# OldETHERNET.net
KiCad netlist of a schematic drawn in Altium Designer
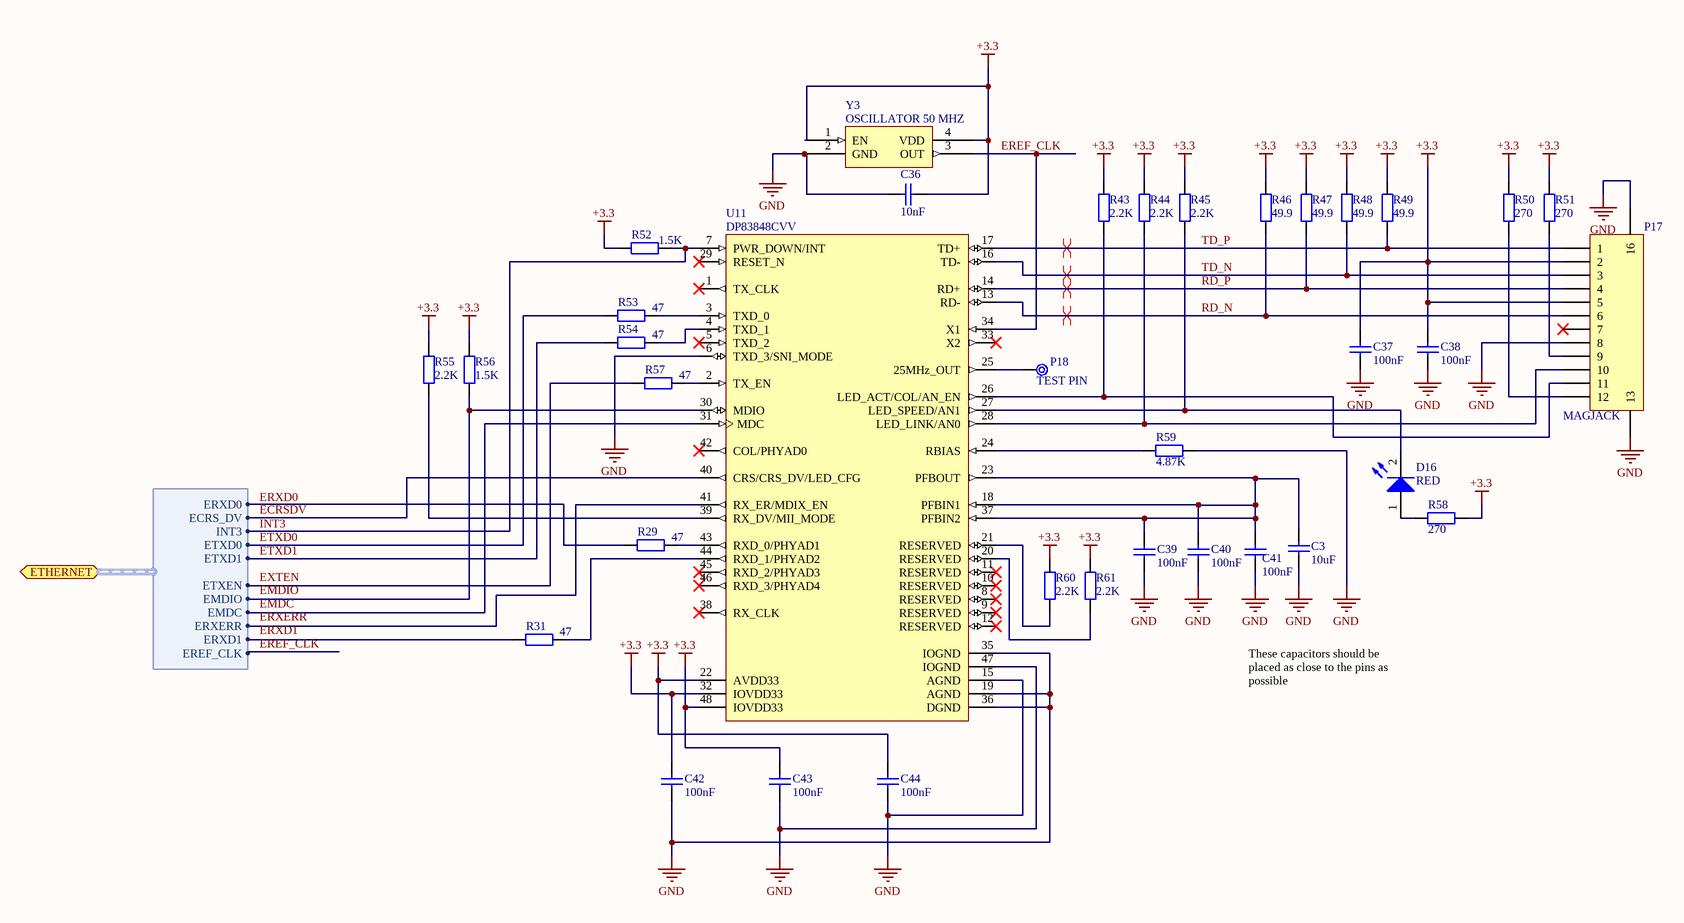
[diagram p0: OldETHERNET.SchDoc]

(export (version "E")
  (design (tool "Eeschema 10.0.6"))
  (components
    (comp (ref "C3")
      (value "10uF")
      (footprint "C0805")
      (description "Capacitor")
      (fields
        (field (name "MANUFACTURER") "YAGEO")
        (field (name "MANUFACTURER PART NUMBER") "CC0805KKX5R5BB106")
      )
      (libsource (lib "BRA") (part "Cap 0805 1uF"))
    )
    (comp (ref "C36")
      (value "10nF")
      (footprint "C0805")
      (description "Capacitor")
      (fields
        (field (name "MANUFACTURER") "MULTICOMP")
        (field (name "MANUFACTURER PART NUMBER") "MC0805B103M500CT")
      )
      (libsource (lib "BRA") (part "Cap 0805 10nF"))
    )
    (comp (ref "C37")
      (value "100nF")
      (footprint "C0805")
      (description "Capacitor")
      (fields
        (field (name "MANUFACTURER") "MULTICOMP")
        (field (name "MANUFACTURER PART NUMBER") "MCCA000296")
      )
      (libsource (lib "BRA") (part "Cap 0805 100nF"))
    )
    (comp (ref "C38")
      (value "100nF")
      (footprint "C0805")
      (description "Capacitor")
      (fields
        (field (name "MANUFACTURER") "MULTICOMP")
        (field (name "MANUFACTURER PART NUMBER") "MCCA000296")
      )
      (libsource (lib "BRA") (part "Cap 0805 100nF"))
    )
    (comp (ref "C39")
      (value "100nF")
      (footprint "C0805")
      (description "Capacitor")
      (fields
        (field (name "MANUFACTURER") "MULTICOMP")
        (field (name "MANUFACTURER PART NUMBER") "MCCA000296")
      )
      (libsource (lib "BRA") (part "Cap 0805 100nF"))
    )
    (comp (ref "C40")
      (value "100nF")
      (footprint "C0805")
      (description "Capacitor")
      (fields
        (field (name "MANUFACTURER") "MULTICOMP")
        (field (name "MANUFACTURER PART NUMBER") "MCCA000296")
      )
      (libsource (lib "BRA") (part "Cap 0805 100nF"))
    )
    (comp (ref "C41")
      (value "100nF")
      (footprint "C0805")
      (description "Capacitor")
      (fields
        (field (name "MANUFACTURER") "MULTICOMP")
        (field (name "MANUFACTURER PART NUMBER") "MCCA000296")
      )
      (libsource (lib "BRA") (part "Cap 0805 100nF"))
    )
    (comp (ref "C42")
      (value "100nF")
      (footprint "C0805")
      (description "Capacitor")
      (fields
        (field (name "MANUFACTURER") "MULTICOMP")
        (field (name "MANUFACTURER PART NUMBER") "MCCA000296")
      )
      (libsource (lib "BRA") (part "Cap 0805 100nF"))
    )
    (comp (ref "C43")
      (value "100nF")
      (footprint "C0805")
      (description "Capacitor")
      (fields
        (field (name "MANUFACTURER") "MULTICOMP")
        (field (name "MANUFACTURER PART NUMBER") "MCCA000296")
      )
      (libsource (lib "BRA") (part "Cap 0805 100nF"))
    )
    (comp (ref "C44")
      (value "100nF")
      (footprint "C0805")
      (description "Capacitor")
      (fields
        (field (name "MANUFACTURER") "MULTICOMP")
        (field (name "MANUFACTURER PART NUMBER") "MCCA000296")
      )
      (libsource (lib "BRA") (part "Cap 0805 100nF"))
    )
    (comp (ref "D16")
      (value "HSMH-C190")
      (footprint "SYLANN:0603-LEDR")
      (description "Surface Mount Chip LED, Red")
      (fields
        (field (name "MANUFACTURER") "AVAGO TECHNOLOGIES")
        (field (name "MANUFACTURER PART NUMBER") "HSMH-C190.")
        (field (name "COULEUR") "RED")
        (field (name "LONGUEUR/HAUTEUR") "1.6")
      )
      (libsource (lib "Avago Optoelectronic LED") (part "HSMH-C190"))
    )
    (comp (ref "P17")
      (value "MAGJACK")
      (footprint "RJ45_8+LED")
      (description "Header, 12-Pin")
      (fields
        (field (name "MANUFACTURER") "STEWART CONNECTOR")
        (field (name "MANUFACTURER PART NUMBER") "SI-60062-F")
        (field (name "PUBLISHER") "Altium Limited")
      )
      (libsource (lib "MAIN BOARD CERES") (part "Header 12"))
    )
    (comp (ref "P18") (value "TEST PIN") (footprint "TP") (libsource (lib "UTIL_Library") (part "TEST PIN")))
    (comp (ref "R29")
      (value "47")
      (footprint "R0805")
      (description "Resistor")
      (fields
        (field (name "MANUFACTURER") "MULTICOMP")
        (field (name "MANUFACTURER PART NUMBER") "MC0063W0603147R")
      )
      (libsource (lib "BRA") (part "Resistor 0805 47"))
    )
    (comp (ref "R31")
      (value "47")
      (footprint "R0805")
      (description "Resistor")
      (fields
        (field (name "MANUFACTURER") "MULTICOMP")
        (field (name "MANUFACTURER PART NUMBER") "MC0063W0603147R")
      )
      (libsource (lib "BRA") (part "Resistor 0805 47"))
    )
    (comp (ref "R43")
      (value "2.2K")
      (footprint "R0805")
      (description "Resistor")
      (fields
        (field (name "MANUFACTURER") "MULTICOMP")
        (field (name "MANUFACTURER PART NUMBER") "MC01W080512K2")
      )
      (libsource (lib "BRA") (part "Resistor 0805 2.2K"))
    )
    (comp (ref "R44")
      (value "2.2K")
      (footprint "R0805")
      (description "Resistor")
      (fields
        (field (name "MANUFACTURER") "MULTICOMP")
        (field (name "MANUFACTURER PART NUMBER") "MC01W080512K2")
      )
      (libsource (lib "BRA") (part "Resistor 0805 2.2K"))
    )
    (comp (ref "R45")
      (value "2.2K")
      (footprint "R0805")
      (description "Resistor")
      (fields
        (field (name "MANUFACTURER") "MULTICOMP")
        (field (name "MANUFACTURER PART NUMBER") "MC01W080512K2")
      )
      (libsource (lib "BRA") (part "Resistor 0805 2.2K"))
    )
    (comp (ref "R46")
      (value "49.9")
      (footprint "R0805")
      (description "Resistor")
      (fields
        (field (name "MANUFACTURER") "MULTICOMP")
        (field (name "MANUFACTURER PART NUMBER") "MC01W0805149R9")
      )
      (libsource (lib "BRA") (part "Resistor 0805 49.9"))
    )
    (comp (ref "R47")
      (value "49.9")
      (footprint "R0805")
      (description "Resistor")
      (fields
        (field (name "MANUFACTURER") "MULTICOMP")
        (field (name "MANUFACTURER PART NUMBER") "MC01W0805149R9")
      )
      (libsource (lib "BRA") (part "Resistor 0805 49.9"))
    )
    (comp (ref "R48")
      (value "49.9")
      (footprint "R0805")
      (description "Resistor")
      (fields
        (field (name "MANUFACTURER") "MULTICOMP")
        (field (name "MANUFACTURER PART NUMBER") "MC01W0805149R9")
      )
      (libsource (lib "BRA") (part "Resistor 0805 49.9"))
    )
    (comp (ref "R49")
      (value "49.9")
      (footprint "R0805")
      (description "Resistor")
      (fields
        (field (name "MANUFACTURER") "MULTICOMP")
        (field (name "MANUFACTURER PART NUMBER") "MC01W0805149R9")
      )
      (libsource (lib "BRA") (part "Resistor 0805 49.9"))
    )
    (comp (ref "R50")
      (value "270")
      (footprint "R0805")
      (description "Resistor")
      (fields
        (field (name "MANUFACTURER") "MULTICOMP")
        (field (name "MANUFACTURER PART NUMBER") "MC01W08051270R")
      )
      (libsource (lib "BRA") (part "Resistor 0805 270"))
    )
    (comp (ref "R51")
      (value "270")
      (footprint "R0805")
      (description "Resistor")
      (fields
        (field (name "MANUFACTURER") "MULTICOMP")
        (field (name "MANUFACTURER PART NUMBER") "MC01W08051270R")
      )
      (libsource (lib "BRA") (part "Resistor 0805 270"))
    )
    (comp (ref "R52")
      (value "1.5K")
      (footprint "R0805")
      (description "Resistor")
      (fields
        (field (name "MANUFACTURER") "MULTICOMP")
        (field (name "MANUFACTURER PART NUMBER") "MC00625W040211K5")
      )
      (libsource (lib "BRA") (part "Resistor 0805 1.5K"))
    )
    (comp (ref "R53")
      (value "47")
      (footprint "R0805")
      (description "Resistor")
      (fields
        (field (name "MANUFACTURER") "MULTICOMP")
        (field (name "MANUFACTURER PART NUMBER") "MC0063W0603147R")
      )
      (libsource (lib "BRA") (part "Resistor 0805 47"))
    )
    (comp (ref "R54")
      (value "47")
      (footprint "R0805")
      (description "Resistor")
      (fields
        (field (name "MANUFACTURER") "MULTICOMP")
        (field (name "MANUFACTURER PART NUMBER") "MC0063W0603147R")
      )
      (libsource (lib "BRA") (part "Resistor 0805 47"))
    )
    (comp (ref "R55")
      (value "2.2K")
      (footprint "R0805")
      (description "Resistor")
      (fields
        (field (name "MANUFACTURER") "MULTICOMP")
        (field (name "MANUFACTURER PART NUMBER") "MC01W080512K2")
      )
      (libsource (lib "BRA") (part "Resistor 0805 2.2K"))
    )
    (comp (ref "R56")
      (value "1.5K")
      (footprint "R0805")
      (description "Resistor")
      (fields
        (field (name "MANUFACTURER") "MULTICOMP")
        (field (name "MANUFACTURER PART NUMBER") "MC00625W040211K5")
      )
      (libsource (lib "") (part "Resistor 0805 1.5K_1"))
    )
    (comp (ref "R57")
      (value "47")
      (footprint "R0805")
      (description "Resistor")
      (fields
        (field (name "MANUFACTURER") "MULTICOMP")
        (field (name "MANUFACTURER PART NUMBER") "MC0063W0603147R")
      )
      (libsource (lib "BRA") (part "Resistor 0805 47"))
    )
    (comp (ref "R58")
      (value "270")
      (footprint "R0805")
      (description "Resistor")
      (fields
        (field (name "MANUFACTURER") "MULTICOMP")
        (field (name "MANUFACTURER PART NUMBER") "MC01W08051270R")
      )
      (libsource (lib "BRA") (part "Resistor 0805 1K"))
    )
    (comp (ref "R59")
      (value "4.87K")
      (footprint "R0805")
      (description "Resistor")
      (fields
        (field (name "MANUFACTURER") "MULTICOMP")
        (field (name "MANUFACTURER PART NUMBER") "MC01W080514K87")
      )
      (libsource (lib "BRA") (part "Resistor 0805"))
    )
    (comp (ref "R60")
      (value "2.2K")
      (footprint "R0805")
      (description "Resistor")
      (fields
        (field (name "MANUFACTURER") "MULTICOMP")
        (field (name "MANUFACTURER PART NUMBER") "MC01W080512K2")
      )
      (libsource (lib "BRA") (part "Resistor 0805 2.2K"))
    )
    (comp (ref "R61")
      (value "2.2K")
      (footprint "R0805")
      (description "Resistor")
      (fields
        (field (name "MANUFACTURER") "MULTICOMP")
        (field (name "MANUFACTURER PART NUMBER") "MC01W080512K2")
      )
      (libsource (lib "BRA") (part "Resistor 0805 2.2K"))
    )
    (comp (ref "U11")
      (value "DP83848CVV")
      (footprint "LLP40P600X600X80_HS-41N")
      (fields
        (field (name "MANUFACTURER") "TEXAS INSTRUMENTS")
        (field (name "MANUFACTURER PART NUMBER") "DP83848MSQ/NOPB")
      )
      (libsource (lib "NSC Interface") (part "DP83848CVV"))
    )
    (comp (ref "Y3")
      (value "OSCILLATOR 50 MHZ")
      (footprint "X3225")
      (description "50 MHZ 3.3Vdc CMOS SMD CRYSTAL CLOCK OSCILLATOR")
      (fields
        (field (name "MANUFACTURER") "ABRACON")
        (field (name "MANUFACTURER PART NUMBER") "ASE-50.000MHZ-LR-T")
      )
      (libsource (lib "BRA") (part "OSCILLLATOR"))
    )
  )
  (nets
    (net (code "2") (name "+3.3") (class "Default")
      (node (ref "C36") (pin "1") (pinfunction "1_1") (pintype "passive"))
      (node (ref "C37") (pin "1") (pinfunction "1_1") (pintype "passive"))
      (node (ref "C38") (pin "1") (pinfunction "1_1") (pintype "passive"))
      (node (ref "C42") (pin "1") (pinfunction "1_1") (pintype "passive"))
      (node (ref "C43") (pin "1") (pinfunction "1_1") (pintype "passive"))
      (node (ref "C44") (pin "1") (pinfunction "1_1") (pintype "passive"))
      (node (ref "P17") (pin "2") (pinfunction "2_2") (pintype "passive"))
      (node (ref "P17") (pin "5") (pinfunction "5_5") (pintype "passive"))
      (node (ref "R43") (pin "2") (pinfunction "2_2") (pintype "passive"))
      (node (ref "R44") (pin "2") (pinfunction "2_2") (pintype "passive"))
      (node (ref "R45") (pin "2") (pinfunction "2_2") (pintype "passive"))
      (node (ref "R46") (pin "2") (pinfunction "2_2") (pintype "passive"))
      (node (ref "R47") (pin "2") (pinfunction "2_2") (pintype "passive"))
      (node (ref "R48") (pin "2") (pinfunction "2_2") (pintype "passive"))
      (node (ref "R49") (pin "2") (pinfunction "2_2") (pintype "passive"))
      (node (ref "R50") (pin "2") (pinfunction "2_2") (pintype "passive"))
      (node (ref "R51") (pin "2") (pinfunction "2_2") (pintype "passive"))
      (node (ref "R52") (pin "2") (pinfunction "2_2") (pintype "passive"))
      (node (ref "R55") (pin "2") (pinfunction "2_2") (pintype "passive"))
      (node (ref "R56") (pin "2") (pinfunction "2_2") (pintype "passive"))
      (node (ref "R58") (pin "1") (pinfunction "1_1") (pintype "passive"))
      (node (ref "R60") (pin "2") (pinfunction "2_2") (pintype "passive"))
      (node (ref "R61") (pin "2") (pinfunction "2_2") (pintype "passive"))
      (node (ref "U11") (pin "22") (pinfunction "AVDD33_22") (pintype "power_in"))
      (node (ref "U11") (pin "32") (pinfunction "IOVDD33_32") (pintype "power_in"))
      (node (ref "U11") (pin "48") (pinfunction "IOVDD33_48") (pintype "power_in"))
      (node (ref "Y3") (pin "1") (pinfunction "EN_1") (pintype "input"))
      (node (ref "Y3") (pin "4") (pinfunction "VDD_4") (pintype "power_in"))
    )
    (net (code "3") (name "/ECRSDV") (class "Default")
      (node (ref "U11") (pin "40") (pinfunction "CRS/CRS_DV/LED_CFG_40") (pintype "output"))
    )
    (net (code "6") (name "/EREF_CLK") (class "Default")
      (node (ref "U11") (pin "34") (pinfunction "X1_34") (pintype "input"))
      (node (ref "Y3") (pin "3") (pinfunction "OUT_3") (pintype "output"))
    )
    (net (code "12") (name "/ETXEN") (class "Default")
      (node (ref "R57") (pin "2") (pinfunction "2_2") (pintype "passive"))
    )
    (net (code "15") (name "/RD_N") (class "Default")
      (node (ref "P17") (pin "6") (pinfunction "6_6") (pintype "passive"))
      (node (ref "R46") (pin "1") (pinfunction "1_1") (pintype "passive"))
      (node (ref "U11") (pin "13") (pinfunction "RD-_13") (pintype "bidirectional"))
    )
    (net (code "16") (name "/RD_P") (class "Default")
      (node (ref "P17") (pin "4") (pinfunction "4_4") (pintype "passive"))
      (node (ref "R47") (pin "1") (pinfunction "1_1") (pintype "passive"))
      (node (ref "U11") (pin "14") (pinfunction "RD+_14") (pintype "bidirectional"))
    )
    (net (code "17") (name "/TD_N") (class "Default")
      (node (ref "P17") (pin "3") (pinfunction "3_3") (pintype "passive"))
      (node (ref "R48") (pin "1") (pinfunction "1_1") (pintype "passive"))
      (node (ref "U11") (pin "16") (pinfunction "TD-_16") (pintype "bidirectional"))
    )
    (net (code "18") (name "/TD_P") (class "Default")
      (node (ref "P17") (pin "1") (pinfunction "1_1") (pintype "passive"))
      (node (ref "R49") (pin "1") (pinfunction "1_1") (pintype "passive"))
      (node (ref "U11") (pin "17") (pinfunction "TD+_17") (pintype "bidirectional"))
    )
    (net (code "20") (name "GND") (class "Default")
      (node (ref "C3") (pin "2") (pinfunction "2_2") (pintype "passive"))
      (node (ref "C36") (pin "2") (pinfunction "2_2") (pintype "passive"))
      (node (ref "C37") (pin "2") (pinfunction "2_2") (pintype "passive"))
      (node (ref "C38") (pin "2") (pinfunction "2_2") (pintype "passive"))
      (node (ref "C39") (pin "2") (pinfunction "2_2") (pintype "passive"))
      (node (ref "C40") (pin "2") (pinfunction "2_2") (pintype "passive"))
      (node (ref "C41") (pin "2") (pinfunction "2_2") (pintype "passive"))
      (node (ref "C42") (pin "2") (pinfunction "2_2") (pintype "passive"))
      (node (ref "C43") (pin "2") (pinfunction "2_2") (pintype "passive"))
      (node (ref "C44") (pin "2") (pinfunction "2_2") (pintype "passive"))
      (node (ref "P17") (pin "13") (pinfunction "13_13") (pintype "passive"))
      (node (ref "P17") (pin "16") (pinfunction "16_16") (pintype "passive"))
      (node (ref "P17") (pin "8") (pinfunction "8_8") (pintype "passive"))
      (node (ref "R59") (pin "1") (pinfunction "1_1") (pintype "passive"))
      (node (ref "U11") (pin "15") (pinfunction "AGND_15") (pintype "power_in"))
      (node (ref "U11") (pin "19") (pinfunction "AGND_19") (pintype "power_in"))
      (node (ref "U11") (pin "35") (pinfunction "IOGND_35") (pintype "power_in"))
      (node (ref "U11") (pin "36") (pinfunction "DGND_36") (pintype "power_in"))
      (node (ref "U11") (pin "47") (pinfunction "IOGND_47") (pintype "power_in"))
      (node (ref "U11") (pin "6") (pinfunction "TXD_3/SNI_MODE_6") (pintype "bidirectional"))
      (node (ref "Y3") (pin "2") (pinfunction "GND_2") (pintype "power_in"))
    )
    (net (code "21") (name "Net-(D16-A)") (class "Default")
      (node (ref "D16") (pin "1") (pinfunction "A_1") (pintype "passive"))
      (node (ref "R58") (pin "2") (pinfunction "2_2") (pintype "passive"))
    )
    (net (code "22") (name "Net-(D16-K)") (class "Default")
      (node (ref "D16") (pin "2") (pinfunction "K_2") (pintype "passive"))
      (node (ref "R45") (pin "1") (pinfunction "1_1") (pintype "passive"))
      (node (ref "U11") (pin "27") (pinfunction "LED_SPEED/AN1_27") (pintype "output"))
    )
    (net (code "23") (name "Net-(P17-Pad9)") (class "Default")
      (node (ref "P17") (pin "9") (pinfunction "9_9") (pintype "passive"))
      (node (ref "R51") (pin "1") (pinfunction "1_1") (pintype "passive"))
    )
    (net (code "24") (name "Net-(P17-Pad12)") (class "Default")
      (node (ref "P17") (pin "12") (pinfunction "12_12") (pintype "passive"))
      (node (ref "R50") (pin "1") (pinfunction "1_1") (pintype "passive"))
    )
    (net (code "25") (name "Net-(R60-Pad1)") (class "Default")
      (node (ref "R60") (pin "1") (pinfunction "1_1") (pintype "passive"))
      (node (ref "U11") (pin "21") (pinfunction "RESERVED_21") (pintype "bidirectional"))
    )
    (net (code "26") (name "Net-(R61-Pad1)") (class "Default")
      (node (ref "R61") (pin "1") (pinfunction "1_1") (pintype "passive"))
      (node (ref "U11") (pin "20") (pinfunction "RESERVED_20") (pintype "bidirectional"))
    )
    (net (code "27") (name "Net-(U11-25MHz_OUT)") (class "Default")
      (node (ref "P18") (pin "1") (pinfunction "1_1") (pintype "passive"))
      (node (ref "U11") (pin "25") (pinfunction "25MHz_OUT_25") (pintype "output"))
    )
    (net (code "28") (name "Net-(U11-LED_ACT{slash}COL{slash}AN_EN)") (class "Default")
      (node (ref "P17") (pin "11") (pinfunction "11_11") (pintype "passive"))
      (node (ref "R43") (pin "1") (pinfunction "1_1") (pintype "passive"))
      (node (ref "U11") (pin "26") (pinfunction "LED_ACT/COL/AN_EN_26") (pintype "output"))
    )
    (net (code "29") (name "Net-(U11-LED_LINK{slash}AN0)") (class "Default")
      (node (ref "P17") (pin "10") (pinfunction "10_10") (pintype "passive"))
      (node (ref "R44") (pin "1") (pinfunction "1_1") (pintype "passive"))
      (node (ref "U11") (pin "28") (pinfunction "LED_LINK/AN0_28") (pintype "output"))
    )
    (net (code "30") (name "Net-(U11-MDIO)") (class "Default")
      (node (ref "R56") (pin "1") (pinfunction "1_1") (pintype "passive"))
      (node (ref "U11") (pin "30") (pinfunction "MDIO_30") (pintype "bidirectional"))
    )
    (net (code "31") (name "Net-(U11-PFBIN1)") (class "Default")
      (node (ref "C3") (pin "1") (pinfunction "1_1") (pintype "passive"))
      (node (ref "C39") (pin "1") (pinfunction "1_1") (pintype "passive"))
      (node (ref "C40") (pin "1") (pinfunction "1_1") (pintype "passive"))
      (node (ref "C41") (pin "1") (pinfunction "1_1") (pintype "passive"))
      (node (ref "U11") (pin "18") (pinfunction "PFBIN1_18") (pintype "input"))
      (node (ref "U11") (pin "23") (pinfunction "PFBOUT_23") (pintype "output"))
      (node (ref "U11") (pin "37") (pinfunction "PFBIN2_37") (pintype "input"))
    )
    (net (code "32") (name "Net-(U11-PWR_DOWN{slash}INT)") (class "Default")
      (node (ref "R52") (pin "1") (pinfunction "1_1") (pintype "passive"))
      (node (ref "U11") (pin "7") (pinfunction "PWR_DOWN/INT_7") (pintype "input"))
    )
    (net (code "33") (name "Net-(U11-RBIAS)") (class "Default")
      (node (ref "R59") (pin "2") (pinfunction "2_2") (pintype "passive"))
      (node (ref "U11") (pin "24") (pinfunction "RBIAS_24") (pintype "input"))
    )
    (net (code "34") (name "Net-(U11-RXD_0{slash}PHYAD1)") (class "Default")
      (node (ref "R29") (pin "1") (pinfunction "1_1") (pintype "passive"))
      (node (ref "U11") (pin "43") (pinfunction "RXD_0/PHYAD1_43") (pintype "output"))
    )
    (net (code "35") (name "Net-(U11-RXD_1{slash}PHYAD2)") (class "Default")
      (node (ref "R31") (pin "1") (pinfunction "1_1") (pintype "passive"))
      (node (ref "U11") (pin "44") (pinfunction "RXD_1/PHYAD2_44") (pintype "output"))
    )
    (net (code "36") (name "Net-(U11-RX_DV{slash}MII_MODE)") (class "Default")
      (node (ref "R55") (pin "1") (pinfunction "1_1") (pintype "passive"))
      (node (ref "U11") (pin "39") (pinfunction "RX_DV/MII_MODE_39") (pintype "output"))
    )
    (net (code "37") (name "Net-(U11-TXD_0)") (class "Default")
      (node (ref "R53") (pin "1") (pinfunction "1_1") (pintype "passive"))
      (node (ref "U11") (pin "3") (pinfunction "TXD_0_3") (pintype "input"))
    )
    (net (code "38") (name "Net-(U11-TXD_1)") (class "Default")
      (node (ref "R54") (pin "1") (pinfunction "1_1") (pintype "passive"))
      (node (ref "U11") (pin "4") (pinfunction "TXD_1_4") (pintype "input"))
    )
    (net (code "39") (name "Net-(U11-TX_EN)") (class "Default")
      (node (ref "R57") (pin "1") (pinfunction "1_1") (pintype "passive"))
      (node (ref "U11") (pin "2") (pinfunction "TX_EN_2") (pintype "input"))
    )
    (net (code "40") (name "unconnected-(P17-Pad7)") (class "Default")
      (node (ref "P17") (pin "7") (pinfunction "7_7") (pintype "passive+no_connect"))
    )
    (net (code "41") (name "unconnected-(R29-Pad2)") (class "Default")
      (node (ref "R29") (pin "2") (pinfunction "2_2") (pintype "passive"))
    )
    (net (code "42") (name "unconnected-(R31-Pad2)") (class "Default")
      (node (ref "R31") (pin "2") (pinfunction "2_2") (pintype "passive"))
    )
    (net (code "43") (name "unconnected-(R53-Pad2)") (class "Default")
      (node (ref "R53") (pin "2") (pinfunction "2_2") (pintype "passive"))
    )
    (net (code "44") (name "unconnected-(R54-Pad2)") (class "Default")
      (node (ref "R54") (pin "2") (pinfunction "2_2") (pintype "passive"))
    )
    (net (code "45") (name "unconnected-(U11-COL{slash}PHYAD0-Pad42)") (class "Default")
      (node (ref "U11") (pin "42") (pinfunction "COL/PHYAD0_42") (pintype "output+no_connect"))
    )
    (net (code "46") (name "unconnected-(U11-MDC-Pad31)") (class "Default")
      (node (ref "U11") (pin "31") (pinfunction "MDC_31") (pintype "input"))
    )
    (net (code "47") (name "unconnected-(U11-RESERVED-Pad8)") (class "Default")
      (node (ref "U11") (pin "8") (pinfunction "RESERVED_8") (pintype "bidirectional+no_connect"))
    )
    (net (code "48") (name "unconnected-(U11-RESERVED-Pad9)") (class "Default")
      (node (ref "U11") (pin "9") (pinfunction "RESERVED_9") (pintype "bidirectional+no_connect"))
    )
    (net (code "49") (name "unconnected-(U11-RESERVED-Pad10)") (class "Default")
      (node (ref "U11") (pin "10") (pinfunction "RESERVED_10") (pintype "bidirectional+no_connect"))
    )
    (net (code "50") (name "unconnected-(U11-RESERVED-Pad11)") (class "Default")
      (node (ref "U11") (pin "11") (pinfunction "RESERVED_11") (pintype "bidirectional+no_connect"))
    )
    (net (code "51") (name "unconnected-(U11-RESERVED-Pad12)") (class "Default")
      (node (ref "U11") (pin "12") (pinfunction "RESERVED_12") (pintype "bidirectional+no_connect"))
    )
    (net (code "52") (name "unconnected-(U11-RESET_N-Pad29)") (class "Default")
      (node (ref "U11") (pin "29") (pinfunction "RESET_N_29") (pintype "input+no_connect"))
    )
    (net (code "53") (name "unconnected-(U11-RXD_2{slash}PHYAD3-Pad45)") (class "Default")
      (node (ref "U11") (pin "45") (pinfunction "RXD_2/PHYAD3_45") (pintype "output+no_connect"))
    )
    (net (code "54") (name "unconnected-(U11-RXD_3{slash}PHYAD4-Pad46)") (class "Default")
      (node (ref "U11") (pin "46") (pinfunction "RXD_3/PHYAD4_46") (pintype "output+no_connect"))
    )
    (net (code "55") (name "unconnected-(U11-RX_CLK-Pad38)") (class "Default")
      (node (ref "U11") (pin "38") (pinfunction "RX_CLK_38") (pintype "output+no_connect"))
    )
    (net (code "56") (name "unconnected-(U11-RX_ER{slash}MDIX_EN-Pad41)") (class "Default")
      (node (ref "U11") (pin "41") (pinfunction "RX_ER/MDIX_EN_41") (pintype "output"))
    )
    (net (code "57") (name "unconnected-(U11-TXD_2-Pad5)") (class "Default")
      (node (ref "U11") (pin "5") (pinfunction "TXD_2_5") (pintype "input+no_connect"))
    )
    (net (code "58") (name "unconnected-(U11-TX_CLK-Pad1)") (class "Default")
      (node (ref "U11") (pin "1") (pinfunction "TX_CLK_1") (pintype "output+no_connect"))
    )
    (net (code "59") (name "unconnected-(U11-X2-Pad33)") (class "Default")
      (node (ref "U11") (pin "33") (pinfunction "X2_33") (pintype "output+no_connect"))
    )
  )
)
